# device.net
KiCad netlist of a schematic drawn in Altium Designer
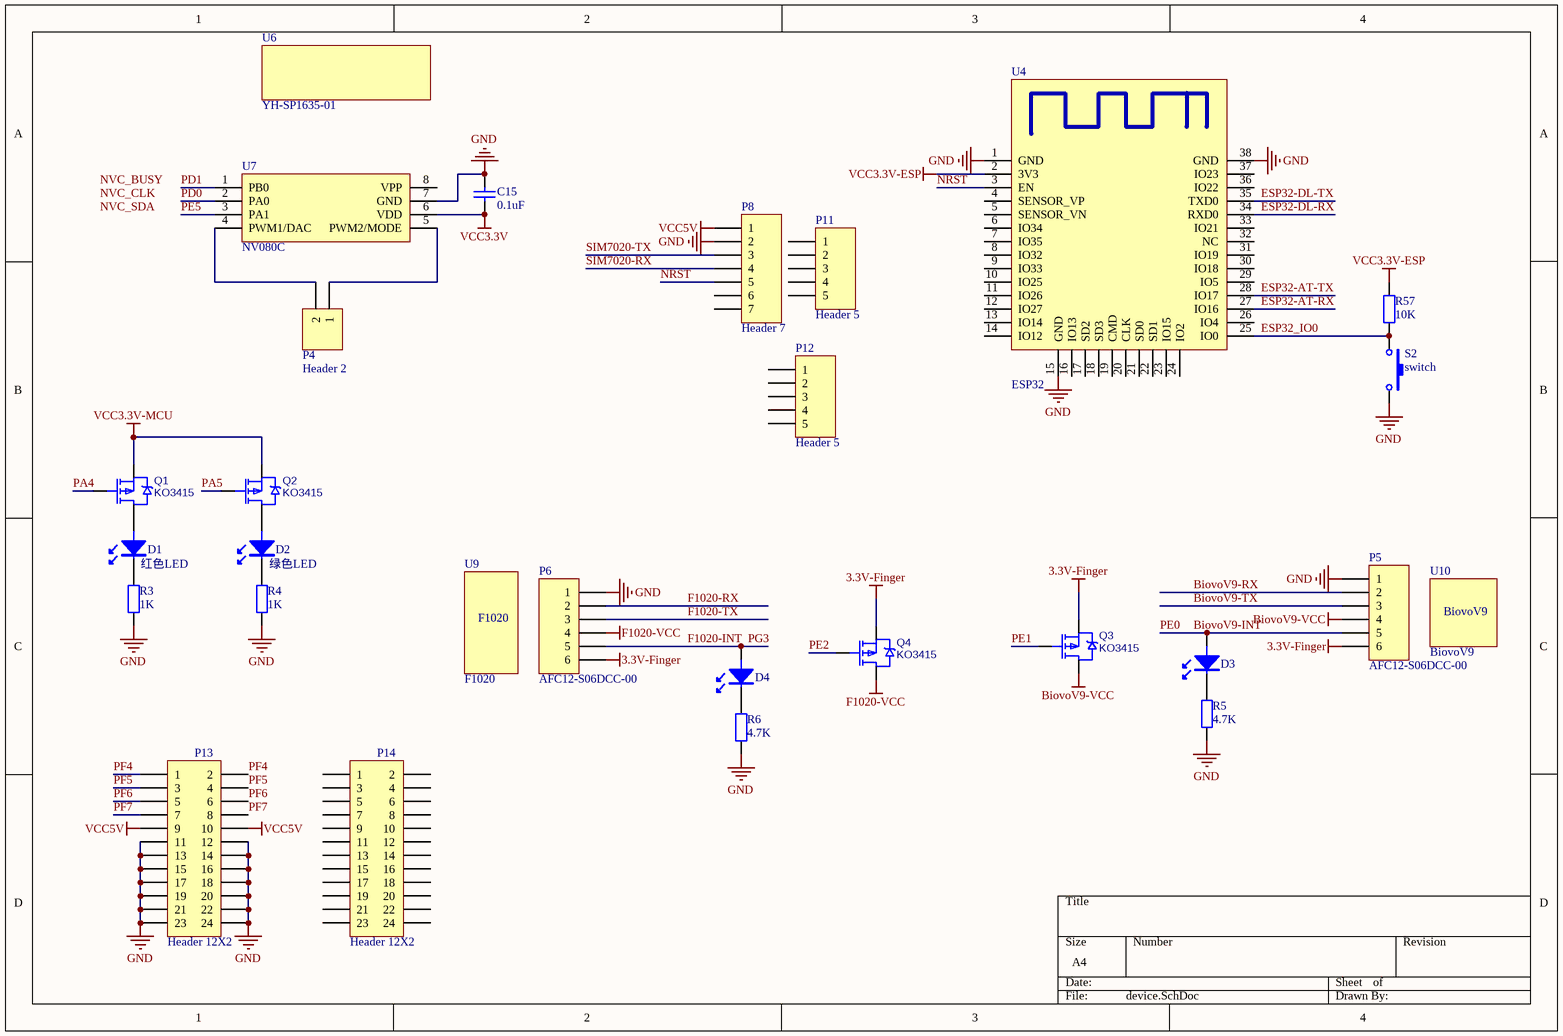
[diagram p0: device.SchDoc]

(export (version "E")
  (design (tool "Eeschema 10.0.6"))
  (components
    (comp (ref "C15")
      (value "0.1uF")
      (footprint "0603_C")
      (description "贴片电容，0603")
      (libsource (lib "stm8l052r8t6开发板") (part "Cap"))
    )
    (comp (ref "D1")
      (value "红色LED")
      (footprint "LED_1206")
      (description "1206封装，红色LED")
      (libsource (lib "stm8l052r8t6开发板") (part "LED"))
    )
    (comp (ref "D2")
      (value "绿色LED")
      (footprint "LED_1206")
      (description "1206封装，绿色LED")
      (libsource (lib "stm8l052r8t6开发板") (part "LED"))
    )
    (comp (ref "D3")
      (value "LED")
      (footprint "0603_LED_S1")
      (description "贴片LED，0603，白色")
      (libsource (lib "stm8l052r8t6开发板") (part "LED"))
    )
    (comp (ref "D4")
      (value "LED")
      (footprint "0603_LED_S1")
      (description "贴片LED，0603，白色")
      (libsource (lib "stm8l052r8t6开发板") (part "LED"))
    )
    (comp (ref "P4")
      (value "Header 2")
      (footprint "HDR1X2")
      (description "不焊")
      (fields (field (name "PUBLISHER") "Altium Limited"))
      (libsource (lib "Miscellaneous Connectors") (part "Header 2"))
    )
    (comp (ref "P5")
      (value "AFC12-S06DCC-00")
      (footprint "CONN-SMD_6PIN_AFC12-S06DCC-00_PITCH1.25-L")
      (description "1.25MM 6P 卧式贴片插座连接器")
      (libsource (lib "") (part "Header 6_1"))
    )
    (comp (ref "P6")
      (value "AFC12-S06DCC-00")
      (footprint "CONN-SMD_6PIN_AFC12-S06DCC-00_PITCH1.25-L")
      (description "1.25MM 6P 卧式贴片插座连接器")
      (libsource (lib "Miscellaneous Connectors") (part "Header 6"))
    )
    (comp (ref "P8")
      (value "Header 7")
      (footprint "HDR1X7")
      (description "Header, 7-Pin")
      (fields (field (name "PUBLISHER") "Altium Limited"))
      (libsource (lib "Miscellaneous Connectors") (part "Header 7"))
    )
    (comp (ref "P11")
      (value "Header 5")
      (footprint "HDR1X5")
      (description "Header, 5-Pin")
      (fields (field (name "PUBLISHER") "Altium Limited"))
      (libsource (lib "Miscellaneous Connectors") (part "Header 5"))
    )
    (comp (ref "P12")
      (value "Header 5")
      (footprint "HDR1X5")
      (description "Header, 5-Pin")
      (fields (field (name "PUBLISHER") "Altium Limited"))
      (libsource (lib "Miscellaneous Connectors") (part "Header 5"))
    )
    (comp (ref "P13")
      (value "Header 12X2")
      (footprint "2.0mm 2*12P直排母")
      (description "Header, 12-Pin, Dual row")
      (fields (field (name "PUBLISHER") "Altium Limited"))
      (libsource (lib "Miscellaneous Connectors") (part "Header 12X2"))
    )
    (comp (ref "P14")
      (value "Header 12X2")
      (footprint "2.0mm 2*12P直排母")
      (description "Header, 12-Pin, Dual row")
      (fields (field (name "PUBLISHER") "Altium Limited"))
      (libsource (lib "Miscellaneous Connectors") (part "Header 12X2"))
    )
    (comp (ref "Q1")
      (value "KO3415")
      (footprint "SOT-23(SOT-23-3)")
      (description "KO3415,SOT23-3")
      (libsource (lib "stm8l052r8t6开发板") (part "3415"))
    )
    (comp (ref "Q2")
      (value "KO3415")
      (footprint "SOT-23(SOT-23-3)")
      (description "KO3415,SOT23-3")
      (libsource (lib "stm8l052r8t6开发板") (part "3415"))
    )
    (comp (ref "Q3")
      (value "KO3415")
      (footprint "SOT-23(SOT-23-3)")
      (description "KO3415,SOT23-3")
      (libsource (lib "stm8l052r8t6开发板") (part "3415"))
    )
    (comp (ref "Q4")
      (value "KO3415")
      (footprint "SOT-23(SOT-23-3)")
      (description "KO3415,SOT23-3")
      (libsource (lib "stm8l052r8t6开发板") (part "3415"))
    )
    (comp (ref "R3")
      (value "1K")
      (footprint "0603_R")
      (description "贴片电阻，0603")
      (libsource (lib "stm8l052r8t6开发板") (part "Res2"))
    )
    (comp (ref "R4")
      (value "1K")
      (footprint "0603_R")
      (description "贴片电阻，0603")
      (libsource (lib "stm8l052r8t6开发板") (part "Res2"))
    )
    (comp (ref "R5")
      (value "4.7K")
      (footprint "0603_R")
      (description "贴片电阻，0603")
      (libsource (lib "stm8l052r8t6开发板") (part "Res2"))
    )
    (comp (ref "R6")
      (value "4.7K")
      (footprint "0603_R")
      (description "贴片电阻，0603")
      (libsource (lib "stm8l052r8t6开发板") (part "Res2"))
    )
    (comp (ref "R57")
      (value "10K")
      (footprint "0603_R")
      (description "贴片电阻，0603")
      (libsource (lib "stm8l052r8t6开发板") (part "Res2"))
    )
    (comp (ref "S2")
      (value "switch")
      (footprint "SW-SMD_4P-L6.2-W6.2-P4.50-LS9.0")
      (description "贴片按键，6*6*5")
      (libsource (lib "stm8l052r8t6开发板") (part "switch"))
    )
    (comp (ref "U4")
      (value "ESP32")
      (footprint "WIFIM-SMD_ESP32-S32MB")
      (libsource (lib "智能锁实践教学平台") (part "ESP32"))
    )
    (comp (ref "U6")
      (value "YH-SP1635-01")
      (footprint "YH-SP1635-01")
      (description "1635腔体喇叭，不焊")
      (libsource (lib "stm8l052r8t6开发板") (part "speaker"))
    )
    (comp (ref "U7")
      (value "NV080C")
      (footprint "SOP-8_150mil")
      (description "语音芯片，SOP-8")
      (libsource (lib "stm8l052r8t6开发板") (part "NVCXXXC"))
    )
    (comp (ref "U9")
      (value "F1020")
      (footprint "F1020")
      (description "不焊")
      (libsource (lib "stm8l052r8t6开发板") (part "F1020"))
    )
    (comp (ref "U10")
      (value "BiovoV9")
      (footprint "BiovoV9")
      (description "不焊")
      (libsource (lib "stm8l052r8t6开发板") (part "BiovoV9"))
    )
  )
  (nets
    (net (code "1") (name "/BiovoV9-INT") (class "Default")
      (node (ref "D3") (pin "A") (pinfunction "A_A") (pintype "passive"))
      (node (ref "P5") (pin "5") (pinfunction "5_5") (pintype "passive"))
    )
    (net (code "2") (name "/BiovoV9-RX") (class "Default")
      (node (ref "P5") (pin "2") (pinfunction "2_2") (pintype "passive"))
    )
    (net (code "3") (name "/BiovoV9-TX") (class "Default")
      (node (ref "P5") (pin "3") (pinfunction "3_3") (pintype "passive"))
    )
    (net (code "4") (name "/ESP32-AT-RX") (class "Default")
      (node (ref "U4") (pin "27") (pinfunction "IO16_27") (pintype "passive"))
    )
    (net (code "5") (name "/ESP32-AT-TX") (class "Default")
      (node (ref "U4") (pin "28") (pinfunction "IO17_28") (pintype "passive"))
    )
    (net (code "6") (name "/ESP32-DL-RX") (class "Default")
      (node (ref "U4") (pin "34") (pinfunction "RXD0_34") (pintype "passive"))
    )
    (net (code "7") (name "/ESP32-DL-TX") (class "Default")
      (node (ref "U4") (pin "35") (pinfunction "TXD0_35") (pintype "passive"))
    )
    (net (code "8") (name "/ESP32_IO0") (class "Default")
      (node (ref "R57") (pin "1") (pinfunction "1_1") (pintype "passive"))
      (node (ref "S2") (pin "1") (pinfunction "1_1") (pintype "passive"))
      (node (ref "U4") (pin "25") (pinfunction "IO0_25") (pintype "passive"))
    )
    (net (code "9") (name "/F1020-INT") (class "Default")
      (node (ref "D4") (pin "A") (pinfunction "A_A") (pintype "passive"))
      (node (ref "P6") (pin "5") (pinfunction "5_5") (pintype "passive"))
    )
    (net (code "10") (name "/F1020-RX") (class "Default")
      (node (ref "P6") (pin "2") (pinfunction "2_2") (pintype "passive"))
    )
    (net (code "11") (name "/F1020-TX") (class "Default")
      (node (ref "P6") (pin "3") (pinfunction "3_3") (pintype "passive"))
    )
    (net (code "12") (name "/NRST") (class "Default")
      (node (ref "P8") (pin "5") (pinfunction "5_5") (pintype "passive"))
      (node (ref "U4") (pin "3") (pinfunction "EN_3") (pintype "passive"))
    )
    (net (code "16") (name "/PA4") (class "Default")
      (node (ref "Q1") (pin "1") (pinfunction "G_1") (pintype "passive"))
    )
    (net (code "17") (name "/PA5") (class "Default")
      (node (ref "Q2") (pin "1") (pinfunction "G_1") (pintype "passive"))
    )
    (net (code "18") (name "/PD0") (class "Default")
      (node (ref "U7") (pin "2") (pinfunction "PA0_2") (pintype "passive"))
    )
    (net (code "19") (name "/PD1") (class "Default")
      (node (ref "U7") (pin "1") (pinfunction "PB0_1") (pintype "passive"))
    )
    (net (code "20") (name "/PE1") (class "Default")
      (node (ref "Q3") (pin "1") (pinfunction "G_1") (pintype "passive"))
    )
    (net (code "21") (name "/PE2") (class "Default")
      (node (ref "Q4") (pin "1") (pinfunction "G_1") (pintype "passive"))
    )
    (net (code "22") (name "/PE5") (class "Default")
      (node (ref "U7") (pin "3") (pinfunction "PA1_3") (pintype "passive"))
    )
    (net (code "23") (name "/PF4") (class "Default")
      (node (ref "P13") (pin "1") (pinfunction "1_1") (pintype "passive"))
      (node (ref "P13") (pin "2") (pinfunction "2_2") (pintype "passive"))
    )
    (net (code "24") (name "/PF5") (class "Default")
      (node (ref "P13") (pin "3") (pinfunction "3_3") (pintype "passive"))
      (node (ref "P13") (pin "4") (pinfunction "4_4") (pintype "passive"))
    )
    (net (code "25") (name "/PF6") (class "Default")
      (node (ref "P13") (pin "5") (pinfunction "5_5") (pintype "passive"))
      (node (ref "P13") (pin "6") (pinfunction "6_6") (pintype "passive"))
    )
    (net (code "26") (name "/PF7") (class "Default")
      (node (ref "P13") (pin "7") (pinfunction "7_7") (pintype "passive"))
      (node (ref "P13") (pin "8") (pinfunction "8_8") (pintype "passive"))
    )
    (net (code "27") (name "/SIM7020-RX") (class "Default")
      (node (ref "P8") (pin "4") (pinfunction "4_4") (pintype "passive"))
    )
    (net (code "28") (name "/SIM7020-TX") (class "Default")
      (node (ref "P8") (pin "3") (pinfunction "3_3") (pintype "passive"))
    )
    (net (code "29") (name "3.3V-Finger") (class "Default")
      (node (ref "P5") (pin "6") (pinfunction "6_6") (pintype "passive"))
      (node (ref "P6") (pin "6") (pinfunction "6_6") (pintype "passive"))
      (node (ref "Q3") (pin "2") (pinfunction "S_2") (pintype "passive"))
      (node (ref "Q4") (pin "2") (pinfunction "S_2") (pintype "passive"))
    )
    (net (code "30") (name "BiovoV9-VCC") (class "Default")
      (node (ref "P5") (pin "4") (pinfunction "4_4") (pintype "passive"))
      (node (ref "Q3") (pin "3") (pinfunction "D_3") (pintype "passive"))
    )
    (net (code "31") (name "F1020-VCC") (class "Default")
      (node (ref "P6") (pin "4") (pinfunction "4_4") (pintype "passive"))
      (node (ref "Q4") (pin "3") (pinfunction "D_3") (pintype "passive"))
    )
    (net (code "32") (name "GND") (class "Default")
      (node (ref "C15") (pin "2") (pinfunction "2_2") (pintype "passive"))
      (node (ref "P13") (pin "11") (pinfunction "11_11") (pintype "passive"))
      (node (ref "P13") (pin "12") (pinfunction "12_12") (pintype "passive"))
      (node (ref "P13") (pin "13") (pinfunction "13_13") (pintype "passive"))
      (node (ref "P13") (pin "14") (pinfunction "14_14") (pintype "passive"))
      (node (ref "P13") (pin "15") (pinfunction "15_15") (pintype "passive"))
      (node (ref "P13") (pin "16") (pinfunction "16_16") (pintype "passive"))
      (node (ref "P13") (pin "17") (pinfunction "17_17") (pintype "passive"))
      (node (ref "P13") (pin "18") (pinfunction "18_18") (pintype "passive"))
      (node (ref "P13") (pin "19") (pinfunction "19_19") (pintype "passive"))
      (node (ref "P13") (pin "20") (pinfunction "20_20") (pintype "passive"))
      (node (ref "P13") (pin "21") (pinfunction "21_21") (pintype "passive"))
      (node (ref "P13") (pin "22") (pinfunction "22_22") (pintype "passive"))
      (node (ref "P13") (pin "23") (pinfunction "23_23") (pintype "passive"))
      (node (ref "P13") (pin "24") (pinfunction "24_24") (pintype "passive"))
      (node (ref "P5") (pin "1") (pinfunction "1_1") (pintype "passive"))
      (node (ref "P6") (pin "1") (pinfunction "1_1") (pintype "passive"))
      (node (ref "P8") (pin "2") (pinfunction "2_2") (pintype "passive"))
      (node (ref "R3") (pin "1") (pinfunction "1_1") (pintype "passive"))
      (node (ref "R4") (pin "1") (pinfunction "1_1") (pintype "passive"))
      (node (ref "R5") (pin "1") (pinfunction "1_1") (pintype "passive"))
      (node (ref "R6") (pin "1") (pinfunction "1_1") (pintype "passive"))
      (node (ref "S2") (pin "2") (pinfunction "2_2") (pintype "passive"))
      (node (ref "U4") (pin "1") (pinfunction "GND_1") (pintype "passive"))
      (node (ref "U4") (pin "15") (pinfunction "GND_15") (pintype "passive"))
      (node (ref "U4") (pin "38") (pinfunction "GND_38") (pintype "passive"))
      (node (ref "U7") (pin "7") (pinfunction "GND_7") (pintype "passive"))
    )
    (net (code "33") (name "Net-(D1-PadK)") (class "Default")
      (node (ref "D1") (pin "K") (pinfunction "K_K") (pintype "passive"))
      (node (ref "R3") (pin "2") (pinfunction "2_2") (pintype "passive"))
    )
    (net (code "34") (name "Net-(D2-PadK)") (class "Default")
      (node (ref "D2") (pin "K") (pinfunction "K_K") (pintype "passive"))
      (node (ref "R4") (pin "2") (pinfunction "2_2") (pintype "passive"))
    )
    (net (code "35") (name "Net-(D3-PadK)") (class "Default")
      (node (ref "D3") (pin "K") (pinfunction "K_K") (pintype "passive"))
      (node (ref "R5") (pin "2") (pinfunction "2_2") (pintype "passive"))
    )
    (net (code "36") (name "Net-(D4-PadK)") (class "Default")
      (node (ref "D4") (pin "K") (pinfunction "K_K") (pintype "passive"))
      (node (ref "R6") (pin "2") (pinfunction "2_2") (pintype "passive"))
    )
    (net (code "37") (name "Net-(Q1-D)") (class "Default")
      (node (ref "D1") (pin "A") (pinfunction "A_A") (pintype "passive"))
      (node (ref "Q1") (pin "3") (pinfunction "D_3") (pintype "passive"))
    )
    (net (code "38") (name "Net-(Q2-D)") (class "Default")
      (node (ref "D2") (pin "A") (pinfunction "A_A") (pintype "passive"))
      (node (ref "Q2") (pin "3") (pinfunction "D_3") (pintype "passive"))
    )
    (net (code "39") (name "Net-(U7-PWM1{slash}DAC)") (class "Default")
      (node (ref "P4") (pin "2") (pinfunction "2_2") (pintype "passive"))
      (node (ref "U7") (pin "4") (pinfunction "PWM1/DAC_4") (pintype "passive"))
    )
    (net (code "40") (name "Net-(U7-PWM2{slash}MODE)") (class "Default")
      (node (ref "P4") (pin "1") (pinfunction "1_1") (pintype "passive"))
      (node (ref "U7") (pin "5") (pinfunction "PWM2/MODE_5") (pintype "passive"))
    )
    (net (code "41") (name "VCC3.3V") (class "Default")
      (node (ref "C15") (pin "1") (pinfunction "1_1") (pintype "passive"))
      (node (ref "U7") (pin "6") (pinfunction "VDD_6") (pintype "passive"))
    )
    (net (code "42") (name "VCC3.3V-ESP") (class "Default")
      (node (ref "R57") (pin "2") (pinfunction "2_2") (pintype "passive"))
      (node (ref "U4") (pin "2") (pinfunction "3V3_2") (pintype "passive"))
    )
    (net (code "43") (name "VCC3.3V-MCU") (class "Default")
      (node (ref "Q1") (pin "2") (pinfunction "S_2") (pintype "passive"))
      (node (ref "Q2") (pin "2") (pinfunction "S_2") (pintype "passive"))
    )
    (net (code "44") (name "VCC5V") (class "Default")
      (node (ref "P13") (pin "10") (pinfunction "10_10") (pintype "passive"))
      (node (ref "P13") (pin "9") (pinfunction "9_9") (pintype "passive"))
      (node (ref "P8") (pin "1") (pinfunction "1_1") (pintype "passive"))
    )
    (net (code "45") (name "unconnected-(P8-Pad6)") (class "Default")
      (node (ref "P8") (pin "6") (pinfunction "6_6") (pintype "passive"))
    )
    (net (code "46") (name "unconnected-(P8-Pad7)") (class "Default")
      (node (ref "P8") (pin "7") (pinfunction "7_7") (pintype "passive"))
    )
    (net (code "47") (name "unconnected-(P11-Pad1)") (class "Default")
      (node (ref "P11") (pin "1") (pinfunction "1_1") (pintype "passive"))
    )
    (net (code "48") (name "unconnected-(P11-Pad2)") (class "Default")
      (node (ref "P11") (pin "2") (pinfunction "2_2") (pintype "passive"))
    )
    (net (code "49") (name "unconnected-(P11-Pad3)") (class "Default")
      (node (ref "P11") (pin "3") (pinfunction "3_3") (pintype "passive"))
    )
    (net (code "50") (name "unconnected-(P11-Pad4)") (class "Default")
      (node (ref "P11") (pin "4") (pinfunction "4_4") (pintype "passive"))
    )
    (net (code "51") (name "unconnected-(P11-Pad5)") (class "Default")
      (node (ref "P11") (pin "5") (pinfunction "5_5") (pintype "passive"))
    )
    (net (code "52") (name "unconnected-(P12-Pad1)") (class "Default")
      (node (ref "P12") (pin "1") (pinfunction "1_1") (pintype "passive"))
    )
    (net (code "53") (name "unconnected-(P12-Pad2)") (class "Default")
      (node (ref "P12") (pin "2") (pinfunction "2_2") (pintype "passive"))
    )
    (net (code "54") (name "unconnected-(P12-Pad3)") (class "Default")
      (node (ref "P12") (pin "3") (pinfunction "3_3") (pintype "passive"))
    )
    (net (code "55") (name "unconnected-(P12-Pad4)") (class "Default")
      (node (ref "P12") (pin "4") (pinfunction "4_4") (pintype "passive"))
    )
    (net (code "56") (name "unconnected-(P12-Pad5)") (class "Default")
      (node (ref "P12") (pin "5") (pinfunction "5_5") (pintype "passive"))
    )
    (net (code "57") (name "unconnected-(P14-Pad1)") (class "Default")
      (node (ref "P14") (pin "1") (pinfunction "1_1") (pintype "passive"))
    )
    (net (code "58") (name "unconnected-(P14-Pad2)") (class "Default")
      (node (ref "P14") (pin "2") (pinfunction "2_2") (pintype "passive"))
    )
    (net (code "59") (name "unconnected-(P14-Pad3)") (class "Default")
      (node (ref "P14") (pin "3") (pinfunction "3_3") (pintype "passive"))
    )
    (net (code "60") (name "unconnected-(P14-Pad4)") (class "Default")
      (node (ref "P14") (pin "4") (pinfunction "4_4") (pintype "passive"))
    )
    (net (code "61") (name "unconnected-(P14-Pad5)") (class "Default")
      (node (ref "P14") (pin "5") (pinfunction "5_5") (pintype "passive"))
    )
    (net (code "62") (name "unconnected-(P14-Pad6)") (class "Default")
      (node (ref "P14") (pin "6") (pinfunction "6_6") (pintype "passive"))
    )
    (net (code "63") (name "unconnected-(P14-Pad7)") (class "Default")
      (node (ref "P14") (pin "7") (pinfunction "7_7") (pintype "passive"))
    )
    (net (code "64") (name "unconnected-(P14-Pad8)") (class "Default")
      (node (ref "P14") (pin "8") (pinfunction "8_8") (pintype "passive"))
    )
    (net (code "65") (name "unconnected-(P14-Pad9)") (class "Default")
      (node (ref "P14") (pin "9") (pinfunction "9_9") (pintype "passive"))
    )
    (net (code "66") (name "unconnected-(P14-Pad10)") (class "Default")
      (node (ref "P14") (pin "10") (pinfunction "10_10") (pintype "passive"))
    )
    (net (code "67") (name "unconnected-(P14-Pad11)") (class "Default")
      (node (ref "P14") (pin "11") (pinfunction "11_11") (pintype "passive"))
    )
    (net (code "68") (name "unconnected-(P14-Pad12)") (class "Default")
      (node (ref "P14") (pin "12") (pinfunction "12_12") (pintype "passive"))
    )
    (net (code "69") (name "unconnected-(P14-Pad13)") (class "Default")
      (node (ref "P14") (pin "13") (pinfunction "13_13") (pintype "passive"))
    )
    (net (code "70") (name "unconnected-(P14-Pad14)") (class "Default")
      (node (ref "P14") (pin "14") (pinfunction "14_14") (pintype "passive"))
    )
    (net (code "71") (name "unconnected-(P14-Pad15)") (class "Default")
      (node (ref "P14") (pin "15") (pinfunction "15_15") (pintype "passive"))
    )
    (net (code "72") (name "unconnected-(P14-Pad16)") (class "Default")
      (node (ref "P14") (pin "16") (pinfunction "16_16") (pintype "passive"))
    )
    (net (code "73") (name "unconnected-(P14-Pad17)") (class "Default")
      (node (ref "P14") (pin "17") (pinfunction "17_17") (pintype "passive"))
    )
    (net (code "74") (name "unconnected-(P14-Pad18)") (class "Default")
      (node (ref "P14") (pin "18") (pinfunction "18_18") (pintype "passive"))
    )
    (net (code "75") (name "unconnected-(P14-Pad19)") (class "Default")
      (node (ref "P14") (pin "19") (pinfunction "19_19") (pintype "passive"))
    )
    (net (code "76") (name "unconnected-(P14-Pad20)") (class "Default")
      (node (ref "P14") (pin "20") (pinfunction "20_20") (pintype "passive"))
    )
    (net (code "77") (name "unconnected-(P14-Pad21)") (class "Default")
      (node (ref "P14") (pin "21") (pinfunction "21_21") (pintype "passive"))
    )
    (net (code "78") (name "unconnected-(P14-Pad22)") (class "Default")
      (node (ref "P14") (pin "22") (pinfunction "22_22") (pintype "passive"))
    )
    (net (code "79") (name "unconnected-(P14-Pad23)") (class "Default")
      (node (ref "P14") (pin "23") (pinfunction "23_23") (pintype "passive"))
    )
    (net (code "80") (name "unconnected-(P14-Pad24)") (class "Default")
      (node (ref "P14") (pin "24") (pinfunction "24_24") (pintype "passive"))
    )
    (net (code "81") (name "unconnected-(U4-CLK-Pad20)") (class "Default")
      (node (ref "U4") (pin "20") (pinfunction "CLK_20") (pintype "passive"))
    )
    (net (code "82") (name "unconnected-(U4-CMD-Pad19)") (class "Default")
      (node (ref "U4") (pin "19") (pinfunction "CMD_19") (pintype "passive"))
    )
    (net (code "83") (name "unconnected-(U4-IO2-Pad24)") (class "Default")
      (node (ref "U4") (pin "24") (pinfunction "IO2_24") (pintype "passive"))
    )
    (net (code "84") (name "unconnected-(U4-IO4-Pad26)") (class "Default")
      (node (ref "U4") (pin "26") (pinfunction "IO4_26") (pintype "passive"))
    )
    (net (code "85") (name "unconnected-(U4-IO5-Pad29)") (class "Default")
      (node (ref "U4") (pin "29") (pinfunction "IO5_29") (pintype "passive"))
    )
    (net (code "86") (name "unconnected-(U4-IO12-Pad14)") (class "Default")
      (node (ref "U4") (pin "14") (pinfunction "IO12_14") (pintype "passive"))
    )
    (net (code "87") (name "unconnected-(U4-IO13-Pad16)") (class "Default")
      (node (ref "U4") (pin "16") (pinfunction "IO13_16") (pintype "passive"))
    )
    (net (code "88") (name "unconnected-(U4-IO14-Pad13)") (class "Default")
      (node (ref "U4") (pin "13") (pinfunction "IO14_13") (pintype "passive"))
    )
    (net (code "89") (name "unconnected-(U4-IO15-Pad23)") (class "Default")
      (node (ref "U4") (pin "23") (pinfunction "IO15_23") (pintype "passive"))
    )
    (net (code "90") (name "unconnected-(U4-IO18-Pad30)") (class "Default")
      (node (ref "U4") (pin "30") (pinfunction "IO18_30") (pintype "passive"))
    )
    (net (code "91") (name "unconnected-(U4-IO19-Pad31)") (class "Default")
      (node (ref "U4") (pin "31") (pinfunction "IO19_31") (pintype "passive"))
    )
    (net (code "92") (name "unconnected-(U4-IO21-Pad33)") (class "Default")
      (node (ref "U4") (pin "33") (pinfunction "IO21_33") (pintype "passive"))
    )
    (net (code "93") (name "unconnected-(U4-IO22-Pad36)") (class "Default")
      (node (ref "U4") (pin "36") (pinfunction "IO22_36") (pintype "passive"))
    )
    (net (code "94") (name "unconnected-(U4-IO23-Pad37)") (class "Default")
      (node (ref "U4") (pin "37") (pinfunction "IO23_37") (pintype "passive"))
    )
    (net (code "95") (name "unconnected-(U4-IO25-Pad10)") (class "Default")
      (node (ref "U4") (pin "10") (pinfunction "IO25_10") (pintype "passive"))
    )
    (net (code "96") (name "unconnected-(U4-IO26-Pad11)") (class "Default")
      (node (ref "U4") (pin "11") (pinfunction "IO26_11") (pintype "passive"))
    )
    (net (code "97") (name "unconnected-(U4-IO27-Pad12)") (class "Default")
      (node (ref "U4") (pin "12") (pinfunction "IO27_12") (pintype "passive"))
    )
    (net (code "98") (name "unconnected-(U4-IO32-Pad8)") (class "Default")
      (node (ref "U4") (pin "8") (pinfunction "IO32_8") (pintype "passive"))
    )
    (net (code "99") (name "unconnected-(U4-IO33-Pad9)") (class "Default")
      (node (ref "U4") (pin "9") (pinfunction "IO33_9") (pintype "passive"))
    )
    (net (code "100") (name "unconnected-(U4-IO34-Pad6)") (class "Default")
      (node (ref "U4") (pin "6") (pinfunction "IO34_6") (pintype "passive"))
    )
    (net (code "101") (name "unconnected-(U4-IO35-Pad7)") (class "Default")
      (node (ref "U4") (pin "7") (pinfunction "IO35_7") (pintype "passive"))
    )
    (net (code "102") (name "unconnected-(U4-NC-Pad32)") (class "Default")
      (node (ref "U4") (pin "32") (pinfunction "NC_32") (pintype "passive"))
    )
    (net (code "103") (name "unconnected-(U4-SD0-Pad21)") (class "Default")
      (node (ref "U4") (pin "21") (pinfunction "SD0_21") (pintype "passive"))
    )
    (net (code "104") (name "unconnected-(U4-SD1-Pad22)") (class "Default")
      (node (ref "U4") (pin "22") (pinfunction "SD1_22") (pintype "passive"))
    )
    (net (code "105") (name "unconnected-(U4-SD2-Pad17)") (class "Default")
      (node (ref "U4") (pin "17") (pinfunction "SD2_17") (pintype "passive"))
    )
    (net (code "106") (name "unconnected-(U4-SD3-Pad18)") (class "Default")
      (node (ref "U4") (pin "18") (pinfunction "SD3_18") (pintype "passive"))
    )
    (net (code "107") (name "unconnected-(U4-SENSOR_VN-Pad5)") (class "Default")
      (node (ref "U4") (pin "5") (pinfunction "SENSOR_VN_5") (pintype "passive"))
    )
    (net (code "108") (name "unconnected-(U4-SENSOR_VP-Pad4)") (class "Default")
      (node (ref "U4") (pin "4") (pinfunction "SENSOR_VP_4") (pintype "passive"))
    )
    (net (code "109") (name "unconnected-(U7-VPP-Pad8)") (class "Default")
      (node (ref "U7") (pin "8") (pinfunction "VPP_8") (pintype "passive"))
    )
  )
)
